# Squib_Managment.net
KiCad netlist of a schematic drawn in Altium Designer
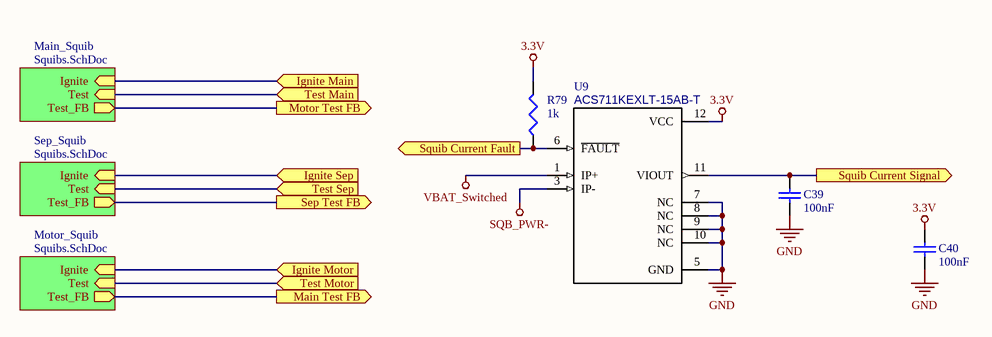
[diagram p0: Squib_Managment.SchDoc]

(export (version "E")
  (design (tool "Eeschema 10.0.6"))
  (components
    (comp (ref "C39")
      (value "100nF")
      (footprint "0805 Footprint")
      (description "Capacitor")
      (fields (field (name "Comment") "Cap") (field (name "PUBLISHER") "Altium Limited"))
      (libsource (lib "Miscellaneous Devices") (part "Cap"))
    )
    (comp (ref "C40")
      (value "100nF")
      (footprint "0805 Footprint")
      (description "Capacitor")
      (fields (field (name "Comment") "Cap") (field (name "PUBLISHER") "Altium Limited"))
      (libsource (lib "Miscellaneous Devices") (part "Cap"))
    )
    (comp (ref "R79")
      (value "1k")
      (description "Resistor")
      (fields (field (name "Comment") "Res3") (field (name "PUBLISHER") "Altium Limited"))
      (libsource (lib "Miscellaneous Devices") (part "Res3"))
    )
    (comp (ref "U9")
      (value "ACS711KEXLT-15AB-T")
      (footprint "*SENSOR_ACS711KEXLT-15AB-T")
      (description "Hall Effect Linear Current Sensor with Overcurrent Fault Output for <100 V Isolation Applications")
      (fields (field (name "MF") "Allegro MicroSystems LLC") (field (name "MP") "ACS711KEXLT-15AB-T"))
      (libsource (lib "AvionicsParts") (part "31A current sensor"))
    )
  )
  (nets
    (net (code "7") (name "/Squib Current Fault") (class "Default")
      (node (ref "R79") (pin "1") (pinfunction "1_1") (pintype "passive"))
      (node (ref "U9") (pin "6") (pinfunction "~{FAULT}_6") (pintype "input"))
    )
    (net (code "8") (name "/Squib Current Signal") (class "Default")
      (node (ref "C39") (pin "2") (pinfunction "2_2") (pintype "passive"))
      (node (ref "U9") (pin "11") (pinfunction "VIOUT_11") (pintype "output"))
    )
    (net (code "12") (name "3.3V") (class "Default")
      (node (ref "C40") (pin "2") (pinfunction "2_2") (pintype "passive"))
      (node (ref "R79") (pin "2") (pinfunction "2_2") (pintype "passive"))
      (node (ref "U9") (pin "12") (pinfunction "VCC_12") (pintype "power_in"))
    )
    (net (code "13") (name "GND") (class "Default")
      (node (ref "C39") (pin "1") (pinfunction "1_1") (pintype "passive"))
      (node (ref "C40") (pin "1") (pinfunction "1_1") (pintype "passive"))
      (node (ref "U9") (pin "10") (pinfunction "NC_10") (pintype "passive"))
      (node (ref "U9") (pin "5") (pinfunction "GND_5") (pintype "power_in"))
      (node (ref "U9") (pin "7") (pinfunction "NC_7") (pintype "passive"))
      (node (ref "U9") (pin "8") (pinfunction "NC_8") (pintype "passive"))
      (node (ref "U9") (pin "9") (pinfunction "NC_9") (pintype "passive"))
    )
    (net (code "14") (name "SQB_PWR-") (class "Default")
      (node (ref "U9") (pin "3") (pinfunction "IP-_3") (pintype "input"))
    )
    (net (code "15") (name "VBAT_Switched") (class "Default")
      (node (ref "U9") (pin "1") (pinfunction "IP+_1") (pintype "input"))
    )
  )
)
